# TwinSensorTestRevB.net
KiCad netlist of a schematic drawn in EAGLE
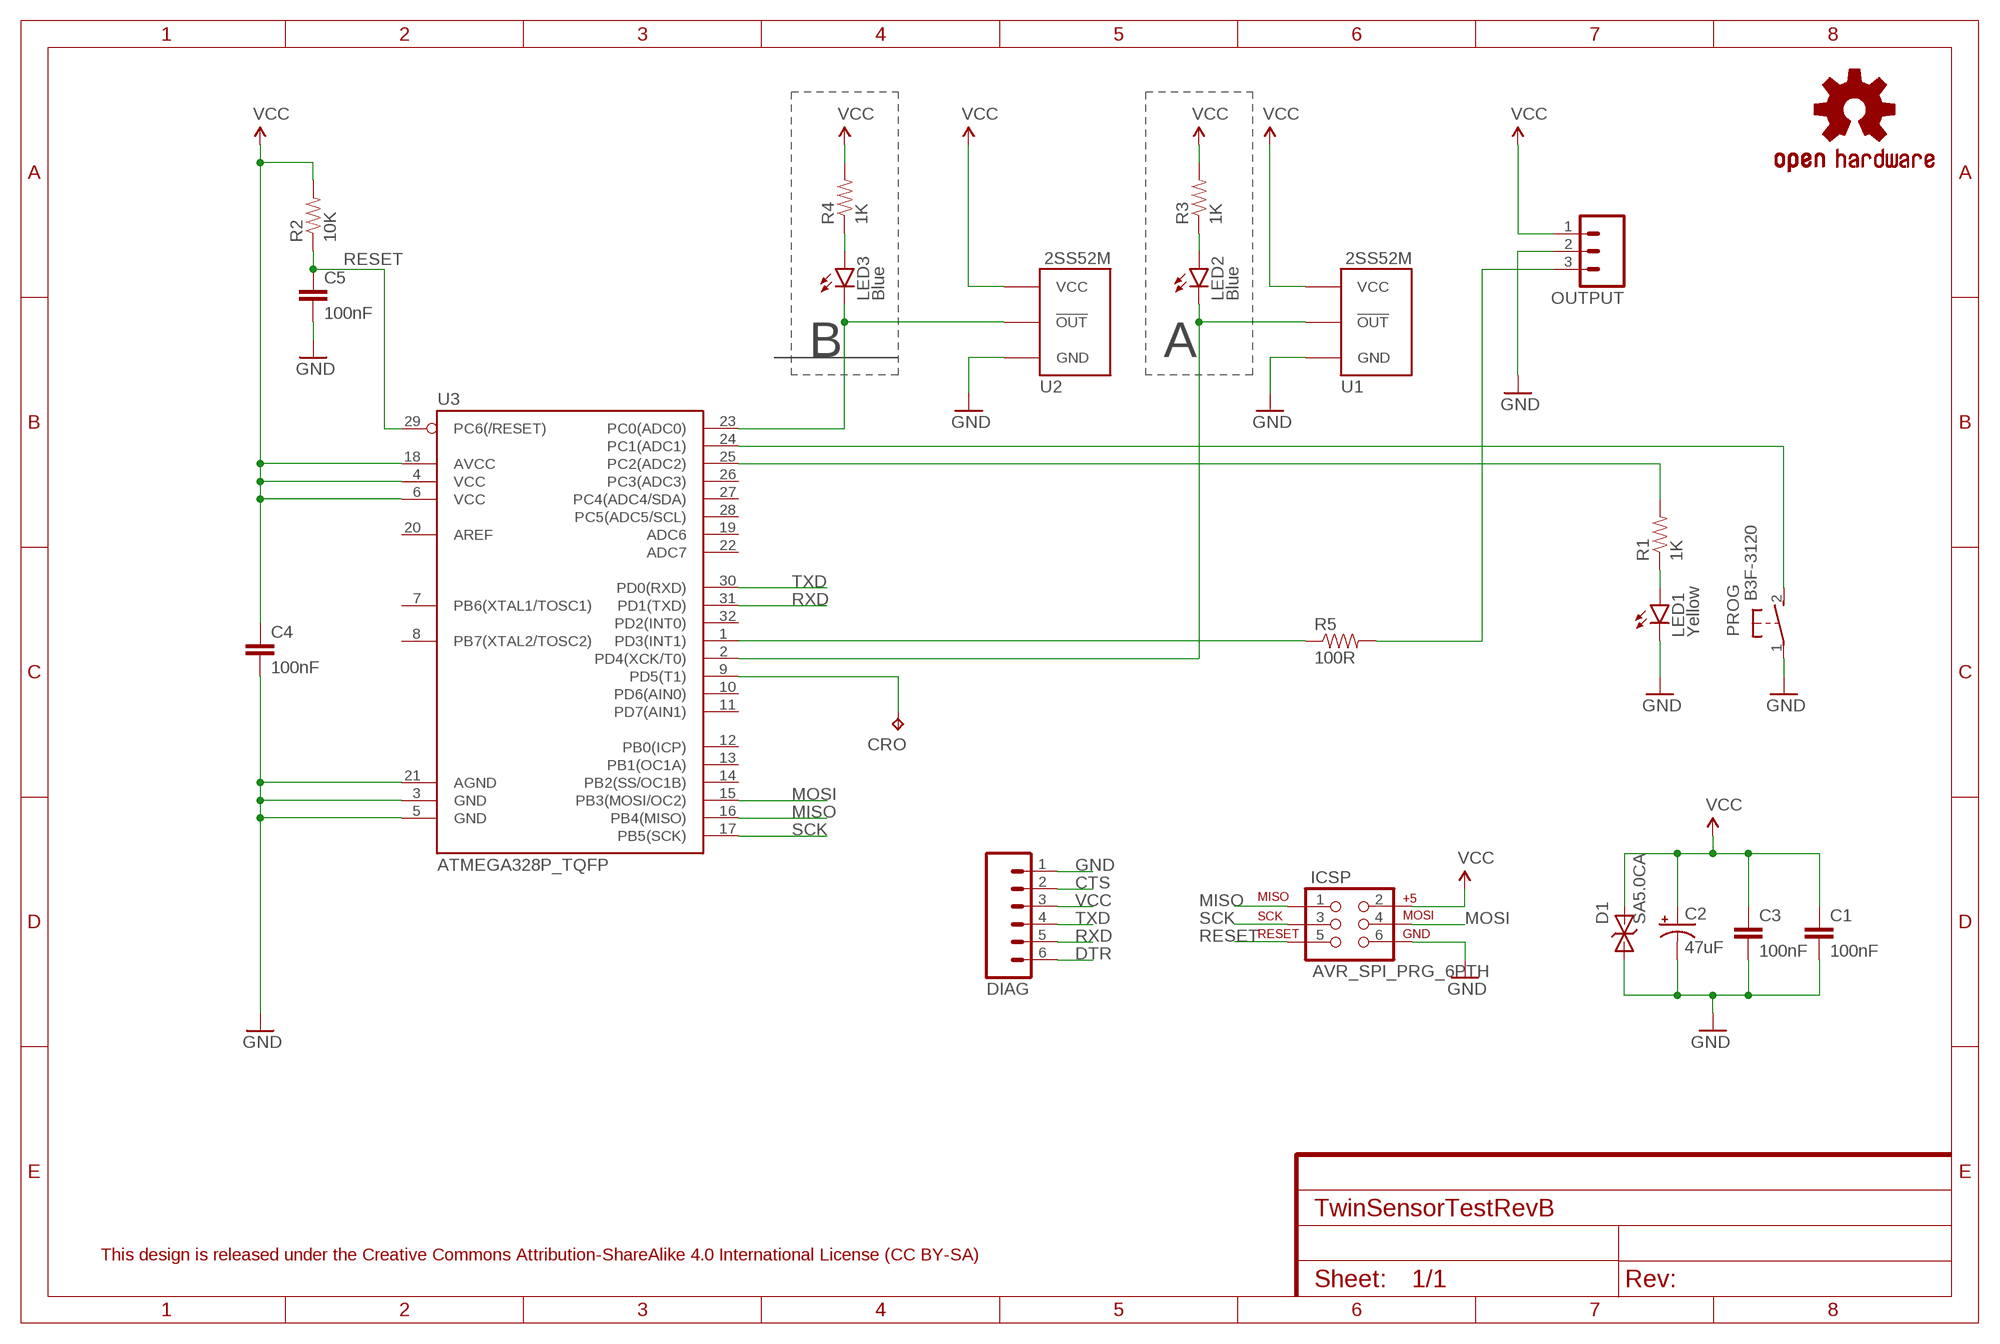
[diagram p0: schematic, sheet 1]

(export (version "E")
  (design (tool "Eeschema 10.0.6"))
  (components
    (comp (ref "C1")
      (value "100nF")
      (footprint "eagle-import:CAP-PTH-SMALL")
      (libsource (lib "eagle-import") (part "CAPPTH"))
    )
    (comp (ref "C2")
      (value "47uF")
      (footprint "eagle-import:CPOL-RADIAL-100UF-25V")
      (libsource (lib "eagle-import") (part "CAP_POLPTH1"))
    )
    (comp (ref "C3")
      (value "100nF")
      (footprint "eagle-import:CAP-PTH-SMALL")
      (libsource (lib "eagle-import") (part "CAPPTH"))
    )
    (comp (ref "C4")
      (value "100nF")
      (footprint "eagle-import:CAP-PTH-SMALL")
      (libsource (lib "eagle-import") (part "CAPPTH"))
    )
    (comp (ref "C5")
      (value "100nF")
      (footprint "eagle-import:CAP-PTH-SMALL")
      (libsource (lib "eagle-import") (part "CAPPTH"))
    )
    (comp (ref "CRO")
      (value "TPTP10R")
      (footprint "eagle-import:TP10R")
      (libsource (lib "eagle-import") (part "TPTP10R"))
    )
    (comp (ref "D1")
      (value "SA5.0CA")
      (footprint "eagle-import:DO41_TVS")
      (libsource (lib "eagle-import") (part "SA5.0CA"))
    )
    (comp (ref "DIAG")
      (value "M06SILK_FEMALE_PTH")
      (footprint "eagle-import:1X06")
      (libsource (lib "eagle-import") (part "M06SILK_FEMALE_PTH"))
    )
    (comp (ref "ICSP")
      (value "AVR_SPI_PRG_6PTH")
      (footprint "eagle-import:2X3")
      (libsource (lib "eagle-import") (part "AVR_SPI_PRG_6PTH"))
    )
    (comp (ref "LED1")
      (value "Yellow")
      (footprint "eagle-import:LED3MM")
      (libsource (lib "eagle-import") (part "LED3MM"))
    )
    (comp (ref "LED2")
      (value "Blue")
      (footprint "eagle-import:LED3MM")
      (libsource (lib "eagle-import") (part "LED3MM"))
    )
    (comp (ref "LED3")
      (value "Blue")
      (footprint "eagle-import:LED3MM")
      (libsource (lib "eagle-import") (part "LED3MM"))
    )
    (comp (ref "LOGO1")
      (value "OSHW-LOGOS")
      (footprint "eagle-import:OSHW-LOGO-S")
      (libsource (lib "eagle-import") (part "OSHW-LOGOS"))
    )
    (comp (ref "OUTPUT")
      (value "M03PTH")
      (footprint "eagle-import:1X03")
      (libsource (lib "eagle-import") (part "M03PTH"))
    )
    (comp (ref "PROG")
      (value "B3F-3120")
      (footprint "eagle-import:B3F-3120")
      (fields (field (name "MPN") "B3F-3100"))
      (libsource (lib "eagle-import") (part "B3F-3120"))
    )
    (comp (ref "R1")
      (value "1K")
      (footprint "eagle-import:AXIAL-0.4")
      (libsource (lib "eagle-import") (part "RESISTORPTH-1/4W"))
    )
    (comp (ref "R2")
      (value "10K")
      (footprint "eagle-import:AXIAL-0.4")
      (libsource (lib "eagle-import") (part "RESISTORPTH-1/4W"))
    )
    (comp (ref "R3")
      (value "1K")
      (footprint "eagle-import:AXIAL-0.4")
      (libsource (lib "eagle-import") (part "RESISTORPTH-1/4W"))
    )
    (comp (ref "R4")
      (value "1K")
      (footprint "eagle-import:AXIAL-0.4")
      (libsource (lib "eagle-import") (part "RESISTORPTH-1/4W"))
    )
    (comp (ref "R5")
      (value "100R")
      (footprint "eagle-import:AXIAL-0.4")
      (libsource (lib "eagle-import") (part "RESISTORPTH-1/4W"))
    )
    (comp (ref "U1")
      (value "2SS52MVERT")
      (footprint "eagle-import:2SS52M_VERT")
      (libsource (lib "eagle-import") (part "2SS52MVERT"))
    )
    (comp (ref "U2")
      (value "2SS52MVERT")
      (footprint "eagle-import:2SS52M_VERT")
      (libsource (lib "eagle-import") (part "2SS52MVERT"))
    )
    (comp (ref "U3")
      (value "ATMEGA328P_TQFP")
      (footprint "eagle-import:TQFP32-08")
      (libsource (lib "eagle-import") (part "ATMEGA328P_TQFP"))
    )
  )
  (nets
    (net (code "1") (name "/CTS") (class "Default")
      (node (ref "DIAG") (pin "2") (pinfunction "2_2") (pintype "passive"))
    )
    (net (code "2") (name "/DTR") (class "Default")
      (node (ref "DIAG") (pin "6") (pinfunction "6_6") (pintype "passive"))
    )
    (net (code "3") (name "/MISO") (class "Default")
      (node (ref "ICSP") (pin "1") (pinfunction "1_1") (pintype "passive"))
      (node (ref "U3") (pin "16") (pinfunction "PB4(MISO)_16") (pintype "bidirectional"))
    )
    (net (code "4") (name "/MOSI") (class "Default")
      (node (ref "ICSP") (pin "4") (pinfunction "4_4") (pintype "passive"))
      (node (ref "U3") (pin "15") (pinfunction "PB3(MOSI/OC2)_15") (pintype "bidirectional"))
    )
    (net (code "5") (name "/RESET") (class "Default")
      (node (ref "C5") (pin "1") (pinfunction "1_1") (pintype "passive"))
      (node (ref "ICSP") (pin "5") (pinfunction "5_5") (pintype "passive"))
      (node (ref "R2") (pin "P$1") (pinfunction "1_P$1") (pintype "passive"))
      (node (ref "U3") (pin "29") (pinfunction "PC6(/RESET)_29") (pintype "bidirectional"))
    )
    (net (code "6") (name "/RXD") (class "Default")
      (node (ref "DIAG") (pin "5") (pinfunction "5_5") (pintype "passive"))
      (node (ref "U3") (pin "31") (pinfunction "PD1(TXD)_31") (pintype "bidirectional"))
    )
    (net (code "7") (name "/SCK") (class "Default")
      (node (ref "ICSP") (pin "3") (pinfunction "3_3") (pintype "passive"))
      (node (ref "U3") (pin "17") (pinfunction "PB5(SCK)_17") (pintype "bidirectional"))
    )
    (net (code "8") (name "/TXD") (class "Default")
      (node (ref "DIAG") (pin "4") (pinfunction "4_4") (pintype "passive"))
      (node (ref "U3") (pin "30") (pinfunction "PD0(RXD)_30") (pintype "bidirectional"))
    )
    (net (code "9") (name "GND") (class "Default")
      (node (ref "C1") (pin "2") (pinfunction "2_2") (pintype "passive"))
      (node (ref "C2") (pin "2") (pinfunction "-_2") (pintype "passive"))
      (node (ref "C3") (pin "2") (pinfunction "2_2") (pintype "passive"))
      (node (ref "C4") (pin "2") (pinfunction "2_2") (pintype "passive"))
      (node (ref "C5") (pin "2") (pinfunction "2_2") (pintype "passive"))
      (node (ref "D1") (pin "A") (pinfunction "A_A") (pintype "passive"))
      (node (ref "DIAG") (pin "1") (pinfunction "1_1") (pintype "passive"))
      (node (ref "ICSP") (pin "6") (pinfunction "6_6") (pintype "passive"))
      (node (ref "LED1") (pin "K") (pinfunction "C_K") (pintype "passive"))
      (node (ref "OUTPUT") (pin "2") (pinfunction "2_2") (pintype "passive"))
      (node (ref "PROG") (pin "1") (pinfunction "P_1") (pintype "passive"))
      (node (ref "U1") (pin "P$1") (pinfunction "GND_P$1") (pintype "bidirectional"))
      (node (ref "U2") (pin "P$1") (pinfunction "GND_P$1") (pintype "bidirectional"))
      (node (ref "U3") (pin "21") (pinfunction "AGND_21") (pintype "bidirectional"))
      (node (ref "U3") (pin "3") (pinfunction "GND_3") (pintype "bidirectional"))
      (node (ref "U3") (pin "5") (pinfunction "GND_5") (pintype "bidirectional"))
    )
    (net (code "10") (name "Net-(LED2-C)") (class "Default")
      (node (ref "LED2") (pin "K") (pinfunction "C_K") (pintype "passive"))
      (node (ref "U1") (pin "P$2") (pinfunction "~{OUT}_P$2") (pintype "bidirectional"))
      (node (ref "U3") (pin "2") (pinfunction "PD4(XCK/T0)_2") (pintype "bidirectional"))
    )
    (net (code "11") (name "Net-(LED3-C)") (class "Default")
      (node (ref "LED3") (pin "K") (pinfunction "C_K") (pintype "passive"))
      (node (ref "U2") (pin "P$2") (pinfunction "~{OUT}_P$2") (pintype "bidirectional"))
      (node (ref "U3") (pin "23") (pinfunction "PC0(ADC0)_23") (pintype "bidirectional"))
    )
    (net (code "12") (name "Net-(PROG-S)") (class "Default")
      (node (ref "PROG") (pin "2") (pinfunction "S_2") (pintype "passive"))
      (node (ref "U3") (pin "24") (pinfunction "PC1(ADC1)_24") (pintype "bidirectional"))
    )
    (net (code "13") (name "Net-(R1-1)") (class "Default")
      (node (ref "LED1") (pin "A") (pinfunction "A_A") (pintype "passive"))
      (node (ref "R1") (pin "P$1") (pinfunction "1_P$1") (pintype "passive"))
    )
    (net (code "14") (name "Net-(R1-2)") (class "Default")
      (node (ref "R1") (pin "P$2") (pinfunction "2_P$2") (pintype "passive"))
      (node (ref "U3") (pin "25") (pinfunction "PC2(ADC2)_25") (pintype "bidirectional"))
    )
    (net (code "15") (name "Net-(R3-1)") (class "Default")
      (node (ref "LED2") (pin "A") (pinfunction "A_A") (pintype "passive"))
      (node (ref "R3") (pin "P$1") (pinfunction "1_P$1") (pintype "passive"))
    )
    (net (code "16") (name "Net-(R4-1)") (class "Default")
      (node (ref "LED3") (pin "A") (pinfunction "A_A") (pintype "passive"))
      (node (ref "R4") (pin "P$1") (pinfunction "1_P$1") (pintype "passive"))
    )
    (net (code "17") (name "Net-(R5-1)") (class "Default")
      (node (ref "R5") (pin "P$1") (pinfunction "1_P$1") (pintype "passive"))
      (node (ref "U3") (pin "1") (pinfunction "PD3(INT1)_1") (pintype "bidirectional"))
    )
    (net (code "18") (name "Net-(R5-2)") (class "Default")
      (node (ref "OUTPUT") (pin "3") (pinfunction "3_3") (pintype "passive"))
      (node (ref "R5") (pin "P$2") (pinfunction "2_P$2") (pintype "passive"))
    )
    (net (code "19") (name "Net-(U3-PD5(T1))") (class "Default")
      (node (ref "CRO") (pin "TP") (pinfunction "TP_TP") (pintype "input"))
      (node (ref "U3") (pin "9") (pinfunction "PD5(T1)_9") (pintype "bidirectional"))
    )
    (net (code "20") (name "VCC") (class "Default")
      (node (ref "C1") (pin "1") (pinfunction "1_1") (pintype "passive"))
      (node (ref "C2") (pin "1") (pinfunction "+_1") (pintype "passive"))
      (node (ref "C3") (pin "1") (pinfunction "1_1") (pintype "passive"))
      (node (ref "C4") (pin "1") (pinfunction "1_1") (pintype "passive"))
      (node (ref "D1") (pin "C") (pinfunction "C_C") (pintype "passive"))
      (node (ref "DIAG") (pin "3") (pinfunction "3_3") (pintype "passive"))
      (node (ref "ICSP") (pin "2") (pinfunction "2_2") (pintype "passive"))
      (node (ref "OUTPUT") (pin "1") (pinfunction "1_1") (pintype "passive"))
      (node (ref "R2") (pin "P$2") (pinfunction "2_P$2") (pintype "passive"))
      (node (ref "R3") (pin "P$2") (pinfunction "2_P$2") (pintype "passive"))
      (node (ref "R4") (pin "P$2") (pinfunction "2_P$2") (pintype "passive"))
      (node (ref "U1") (pin "P$3") (pinfunction "VCC_P$3") (pintype "bidirectional"))
      (node (ref "U2") (pin "P$3") (pinfunction "VCC_P$3") (pintype "bidirectional"))
      (node (ref "U3") (pin "18") (pinfunction "AVCC_18") (pintype "bidirectional"))
      (node (ref "U3") (pin "4") (pinfunction "VCC_4") (pintype "bidirectional"))
      (node (ref "U3") (pin "6") (pinfunction "VCC_6") (pintype "bidirectional"))
    )
    (net (code "21") (name "unconnected-(U3-ADC6-Pad19)") (class "Default")
      (node (ref "U3") (pin "19") (pinfunction "ADC6_19") (pintype "bidirectional"))
    )
    (net (code "22") (name "unconnected-(U3-ADC7-Pad22)") (class "Default")
      (node (ref "U3") (pin "22") (pinfunction "ADC7_22") (pintype "bidirectional"))
    )
    (net (code "23") (name "unconnected-(U3-AREF-Pad20)") (class "Default")
      (node (ref "U3") (pin "20") (pinfunction "AREF_20") (pintype "bidirectional"))
    )
    (net (code "24") (name "unconnected-(U3-PB0(ICP)-Pad12)") (class "Default")
      (node (ref "U3") (pin "12") (pinfunction "PB0(ICP)_12") (pintype "bidirectional"))
    )
    (net (code "25") (name "unconnected-(U3-PB1(OC1A)-Pad13)") (class "Default")
      (node (ref "U3") (pin "13") (pinfunction "PB1(OC1A)_13") (pintype "bidirectional"))
    )
    (net (code "26") (name "unconnected-(U3-PB2(SS{slash}OC1B)-Pad14)") (class "Default")
      (node (ref "U3") (pin "14") (pinfunction "PB2(SS/OC1B)_14") (pintype "bidirectional"))
    )
    (net (code "27") (name "unconnected-(U3-PB6(XTAL1{slash}TOSC1)-Pad7)") (class "Default")
      (node (ref "U3") (pin "7") (pinfunction "PB6(XTAL1/TOSC1)_7") (pintype "bidirectional"))
    )
    (net (code "28") (name "unconnected-(U3-PB7(XTAL2{slash}TOSC2)-Pad8)") (class "Default")
      (node (ref "U3") (pin "8") (pinfunction "PB7(XTAL2/TOSC2)_8") (pintype "bidirectional"))
    )
    (net (code "29") (name "unconnected-(U3-PC3(ADC3)-Pad26)") (class "Default")
      (node (ref "U3") (pin "26") (pinfunction "PC3(ADC3)_26") (pintype "bidirectional"))
    )
    (net (code "30") (name "unconnected-(U3-PC4(ADC4{slash}SDA)-Pad27)") (class "Default")
      (node (ref "U3") (pin "27") (pinfunction "PC4(ADC4/SDA)_27") (pintype "bidirectional"))
    )
    (net (code "31") (name "unconnected-(U3-PC5(ADC5{slash}SCL)-Pad28)") (class "Default")
      (node (ref "U3") (pin "28") (pinfunction "PC5(ADC5/SCL)_28") (pintype "bidirectional"))
    )
    (net (code "32") (name "unconnected-(U3-PD2(INT0)-Pad32)") (class "Default")
      (node (ref "U3") (pin "32") (pinfunction "PD2(INT0)_32") (pintype "bidirectional"))
    )
    (net (code "33") (name "unconnected-(U3-PD6(AIN0)-Pad10)") (class "Default")
      (node (ref "U3") (pin "10") (pinfunction "PD6(AIN0)_10") (pintype "bidirectional"))
    )
    (net (code "34") (name "unconnected-(U3-PD7(AIN1)-Pad11)") (class "Default")
      (node (ref "U3") (pin "11") (pinfunction "PD7(AIN1)_11") (pintype "bidirectional"))
    )
  )
)
